# USB_OTG_FS.net
KiCad netlist of a schematic drawn in Altium Designer
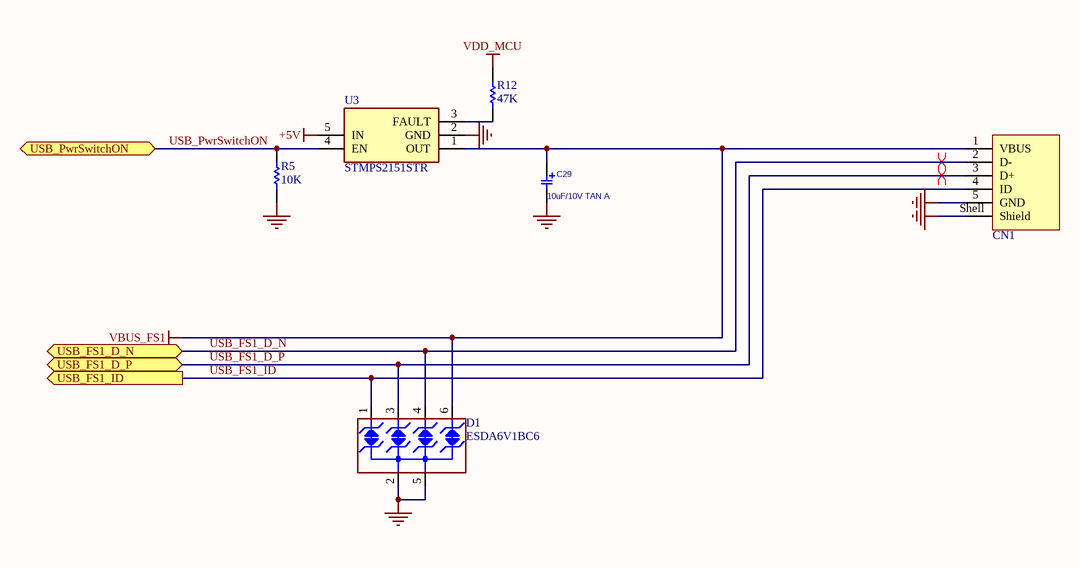
[diagram p0: USB_OTG_FS.SchDoc]

(export (version "E")
  (design (tool "Eeschema 10.0.6"))
  (components
    (comp (ref "C29")
      (value "10uF/10V TAN A")
      (footprint "C_TN_3216")
      (description "CAP, SMD, TAN")
      (fields (field (name "MANF") "VISHAY") (field (name "MANF_P#") "T55A106M6R3C0300"))
      (libsource (lib "CapTantal_passive") (part "CAP_SMD_TAN_10uF_6.3V"))
    )
    (comp (ref "CN1")
      (value "651005136421")
      (footprint "651005136421")
      (description "WR-COM Mini USB 2.0 Type B Vertical 5 Contacts")
      (fields (field (name "MANUFACTURER") "Wurth Elektronik"))
      (libsource (lib "WE - Electromechanical Components") (part "Mini USB 2.0_Type B_Receptacle_1 Port"))
    )
    (comp (ref "D1")
      (value "ESDA6V1BC6")
      (footprint "SOT95P280X145-6N")
      (description "4-line ESD protection")
      (libsource (lib "MB1137") (part "ESDA6V1BC6"))
    )
    (comp (ref "R5")
      (value "10K")
      (footprint "R0603")
      (fields (field (name "PUBLISHER") "Altium Limited"))
      (libsource (lib "Miscellaneous Devices") (part "res1"))
    )
    (comp (ref "R12")
      (value "47K")
      (footprint "R0603")
      (fields (field (name "PUBLISHER") "Altium Limited"))
      (libsource (lib "Miscellaneous Devices") (part "res1"))
    )
    (comp (ref "U3")
      (value "STMPS2151STR")
      (footprint "SOT95P280X145-5N")
      (description "Integrated Circuit")
      (libsource (lib "*") (part "STMPS2151STR"))
    )
  )
  (nets
    (net (code "1") (name "+5V") (class "Default")
      (node (ref "U3") (pin "5") (pinfunction "IN_5") (pintype "passive"))
    )
    (net (code "2") (name "/USB_FS1_D_N") (class "Default")
      (node (ref "CN1") (pin "2") (pinfunction "D-_2") (pintype "passive"))
      (node (ref "D1") (pin "4") (pinfunction "IO3_4") (pintype "passive"))
    )
    (net (code "3") (name "/USB_FS1_D_P") (class "Default")
      (node (ref "CN1") (pin "3") (pinfunction "D+_3") (pintype "passive"))
      (node (ref "D1") (pin "3") (pinfunction "GND_3") (pintype "passive"))
    )
    (net (code "4") (name "/USB_FS1_ID") (class "Default")
      (node (ref "CN1") (pin "4") (pinfunction "ID_4") (pintype "passive"))
      (node (ref "D1") (pin "1") (pinfunction "IO1_1") (pintype "passive"))
    )
    (net (code "5") (name "/USB_PwrSwitchON") (class "Default")
      (node (ref "R5") (pin "1") (pinfunction "1_1") (pintype "passive"))
      (node (ref "U3") (pin "4") (pinfunction "EN_4") (pintype "passive"))
    )
    (net (code "6") (name "GND") (class "Default")
      (node (ref "C29") (pin "2") (pinfunction "2_2") (pintype "passive"))
      (node (ref "CN1") (pin "5") (pinfunction "GND_5") (pintype "passive"))
      (node (ref "CN1") (pin "Shell") (pinfunction "Shield_Shell") (pintype "passive"))
      (node (ref "D1") (pin "2") (pinfunction "IO2_2") (pintype "passive"))
      (node (ref "D1") (pin "5") (pinfunction "IO4_5") (pintype "passive"))
      (node (ref "R5") (pin "2") (pinfunction "2_2") (pintype "passive"))
      (node (ref "U3") (pin "2") (pinfunction "GND_2") (pintype "passive"))
    )
    (net (code "7") (name "Net-(U3-FAULT)") (class "Default")
      (node (ref "R12") (pin "2") (pinfunction "2_2") (pintype "passive"))
      (node (ref "U3") (pin "3") (pinfunction "FAULT_3") (pintype "passive"))
    )
    (net (code "8") (name "VBUS_FS1") (class "Default")
      (node (ref "C29") (pin "1") (pinfunction "1_1") (pintype "passive"))
      (node (ref "CN1") (pin "1") (pinfunction "VBUS_1") (pintype "passive"))
      (node (ref "D1") (pin "6") (pinfunction "NC_6") (pintype "passive"))
      (node (ref "U3") (pin "1") (pinfunction "OUT_1") (pintype "passive"))
    )
    (net (code "9") (name "VDD_MCU") (class "Default")
      (node (ref "R12") (pin "1") (pinfunction "1_1") (pintype "passive"))
    )
  )
)
